# converter.net
KiCad netlist of a schematic drawn in EAGLE
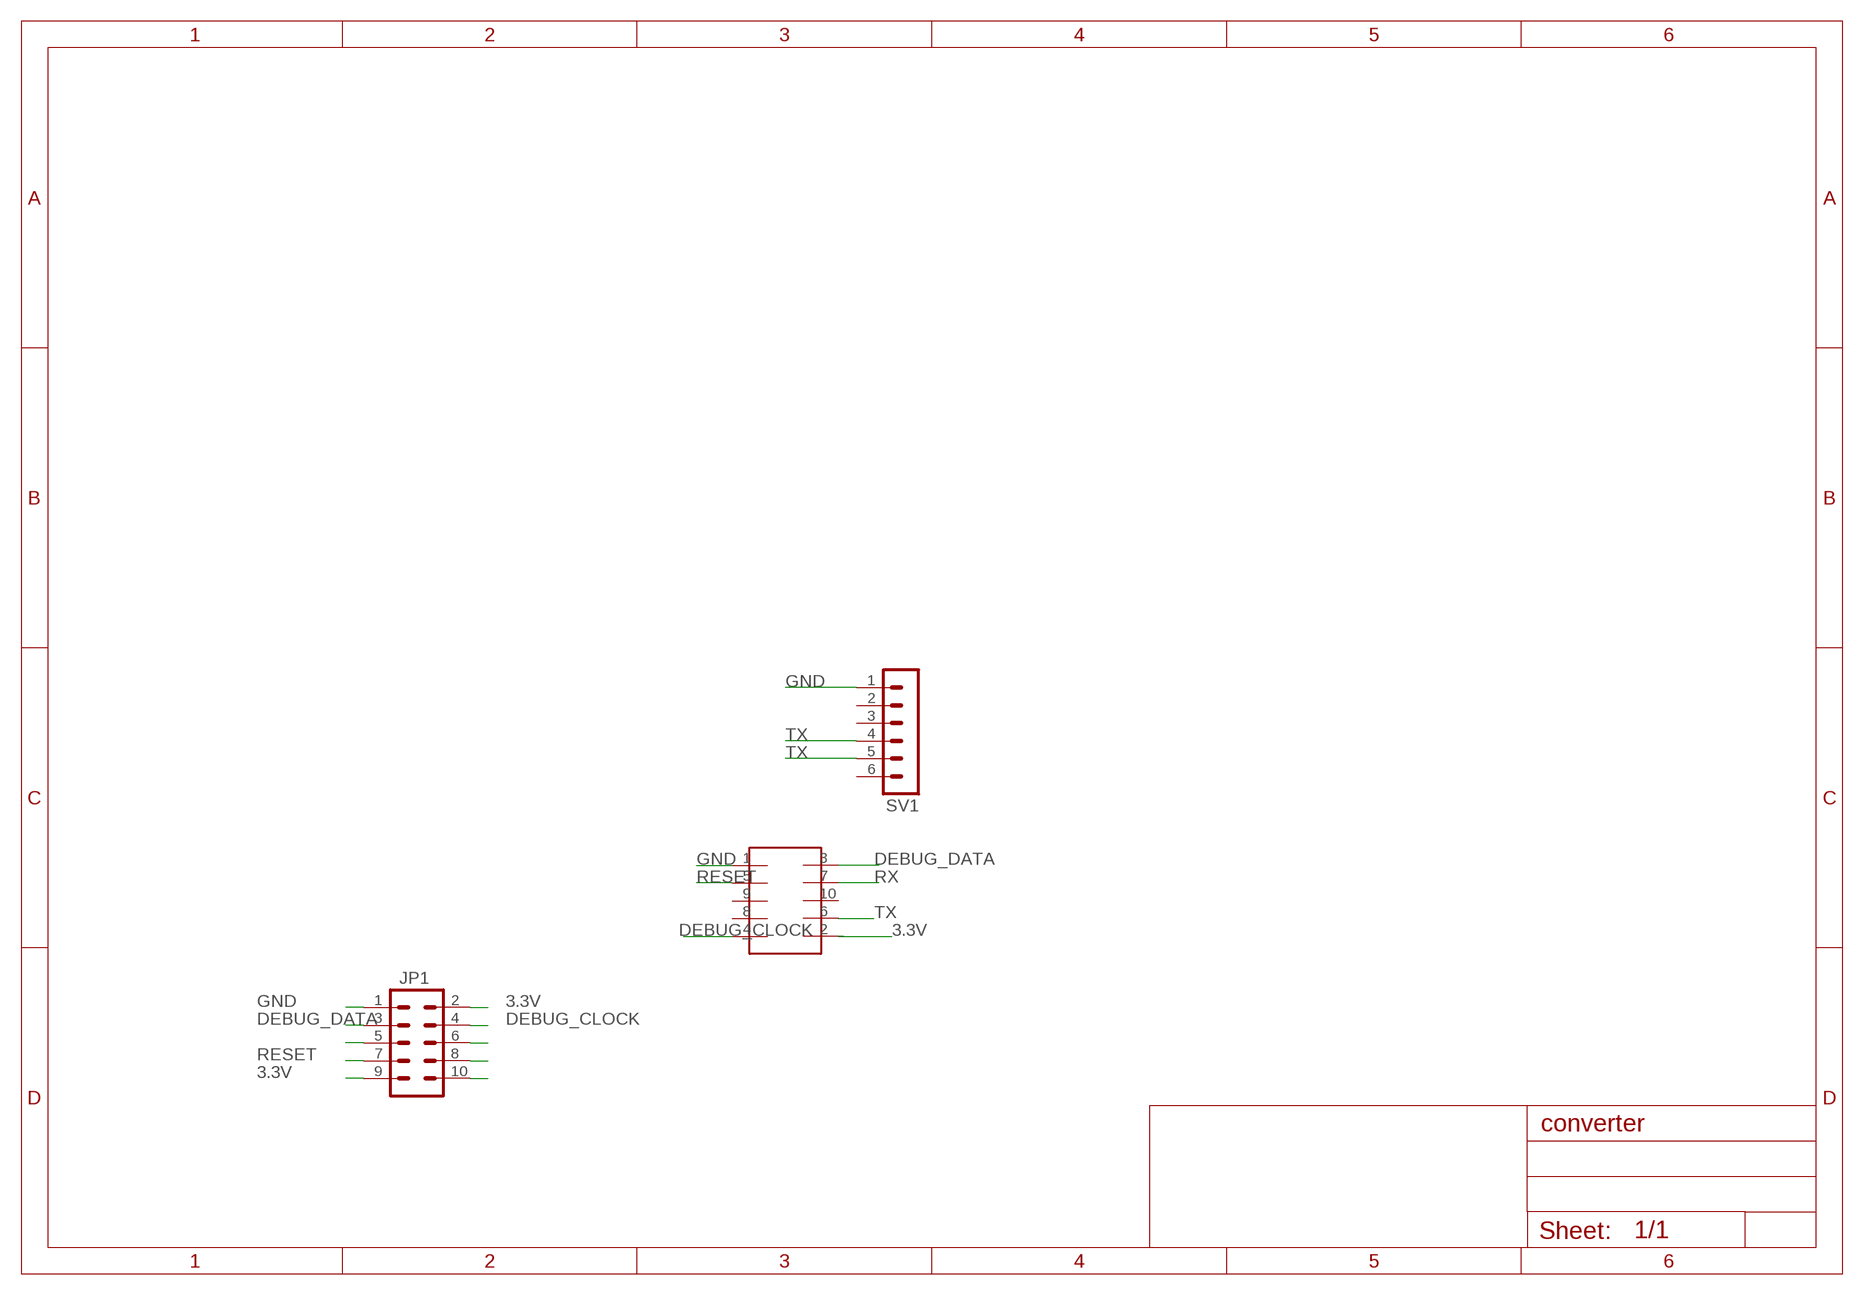
[diagram p0: schematic, sheet 1]

(export (version "E")
  (design (tool "Eeschema 10.0.6"))
  (components
    (comp (ref "JP1")
      (value "M05X2SHD")
      (footprint "eagle-import:2X5-SHROUDED")
      (libsource (lib "eagle-import") (part "M05X2SHD"))
    )
    (comp (ref "SV1")
      (value "MA06-1")
      (footprint "eagle-import:MA06-1")
      (libsource (lib "eagle-import") (part "MA06-1"))
    )
    (comp (ref "U$4")
      (value "TC-2050-SOCKET")
      (footprint "eagle-import:TC-2050-SOCKET")
      (libsource (lib "eagle-import") (part "TC-2050-SOCKET"))
    )
  )
  (nets
    (net (code "1") (name "/3.3V") (class "Default")
      (node (ref "JP1") (pin "2") (pinfunction "2_2") (pintype "passive"))
      (node (ref "JP1") (pin "9") (pinfunction "9_9") (pintype "passive"))
      (node (ref "U$4") (pin "2") (pinfunction "2_2") (pintype "bidirectional"))
    )
    (net (code "2") (name "/DEBUG_CLOCK") (class "Default")
      (node (ref "JP1") (pin "4") (pinfunction "4_4") (pintype "passive"))
      (node (ref "U$4") (pin "4") (pinfunction "4_4") (pintype "bidirectional"))
    )
    (net (code "3") (name "/DEBUG_DATA") (class "Default")
      (node (ref "JP1") (pin "3") (pinfunction "3_3") (pintype "passive"))
      (node (ref "U$4") (pin "3") (pinfunction "3_3") (pintype "bidirectional"))
    )
    (net (code "4") (name "/GND") (class "Default")
      (node (ref "JP1") (pin "1") (pinfunction "1_1") (pintype "passive"))
      (node (ref "SV1") (pin "1") (pinfunction "1_1") (pintype "passive"))
      (node (ref "U$4") (pin "1") (pinfunction "1_1") (pintype "bidirectional"))
    )
    (net (code "5") (name "/RESET") (class "Default")
      (node (ref "JP1") (pin "7") (pinfunction "7_7") (pintype "passive"))
      (node (ref "U$4") (pin "5") (pinfunction "5_5") (pintype "bidirectional"))
    )
    (net (code "6") (name "/RX") (class "Default")
      (node (ref "U$4") (pin "7") (pinfunction "7_7") (pintype "bidirectional"))
    )
    (net (code "7") (name "/TX") (class "Default")
      (node (ref "SV1") (pin "4") (pinfunction "4_4") (pintype "passive"))
      (node (ref "SV1") (pin "5") (pinfunction "5_5") (pintype "passive"))
      (node (ref "U$4") (pin "6") (pinfunction "6_6") (pintype "bidirectional"))
    )
    (net (code "8") (name "unconnected-(JP1-Pad5)") (class "Default")
      (node (ref "JP1") (pin "5") (pinfunction "5_5") (pintype "passive"))
    )
    (net (code "9") (name "unconnected-(JP1-Pad6)") (class "Default")
      (node (ref "JP1") (pin "6") (pinfunction "6_6") (pintype "passive"))
    )
    (net (code "10") (name "unconnected-(JP1-Pad8)") (class "Default")
      (node (ref "JP1") (pin "8") (pinfunction "8_8") (pintype "passive"))
    )
    (net (code "11") (name "unconnected-(JP1-Pad10)") (class "Default")
      (node (ref "JP1") (pin "10") (pinfunction "10_10") (pintype "passive"))
    )
    (net (code "12") (name "unconnected-(SV1-Pad2)") (class "Default")
      (node (ref "SV1") (pin "2") (pinfunction "2_2") (pintype "passive"))
    )
    (net (code "13") (name "unconnected-(SV1-Pad3)") (class "Default")
      (node (ref "SV1") (pin "3") (pinfunction "3_3") (pintype "passive"))
    )
    (net (code "14") (name "unconnected-(SV1-Pad6)") (class "Default")
      (node (ref "SV1") (pin "6") (pinfunction "6_6") (pintype "passive"))
    )
    (net (code "15") (name "unconnected-(U$4-Pad8)") (class "Default")
      (node (ref "U$4") (pin "8") (pinfunction "8_8") (pintype "bidirectional"))
    )
    (net (code "16") (name "unconnected-(U$4-Pad9)") (class "Default")
      (node (ref "U$4") (pin "9") (pinfunction "9_9") (pintype "bidirectional"))
    )
    (net (code "17") (name "unconnected-(U$4-Pad10)") (class "Default")
      (node (ref "U$4") (pin "10") (pinfunction "10_10") (pintype "bidirectional"))
    )
  )
)
